# Microcontroleur.net
KiCad netlist of a schematic drawn in Altium Designer
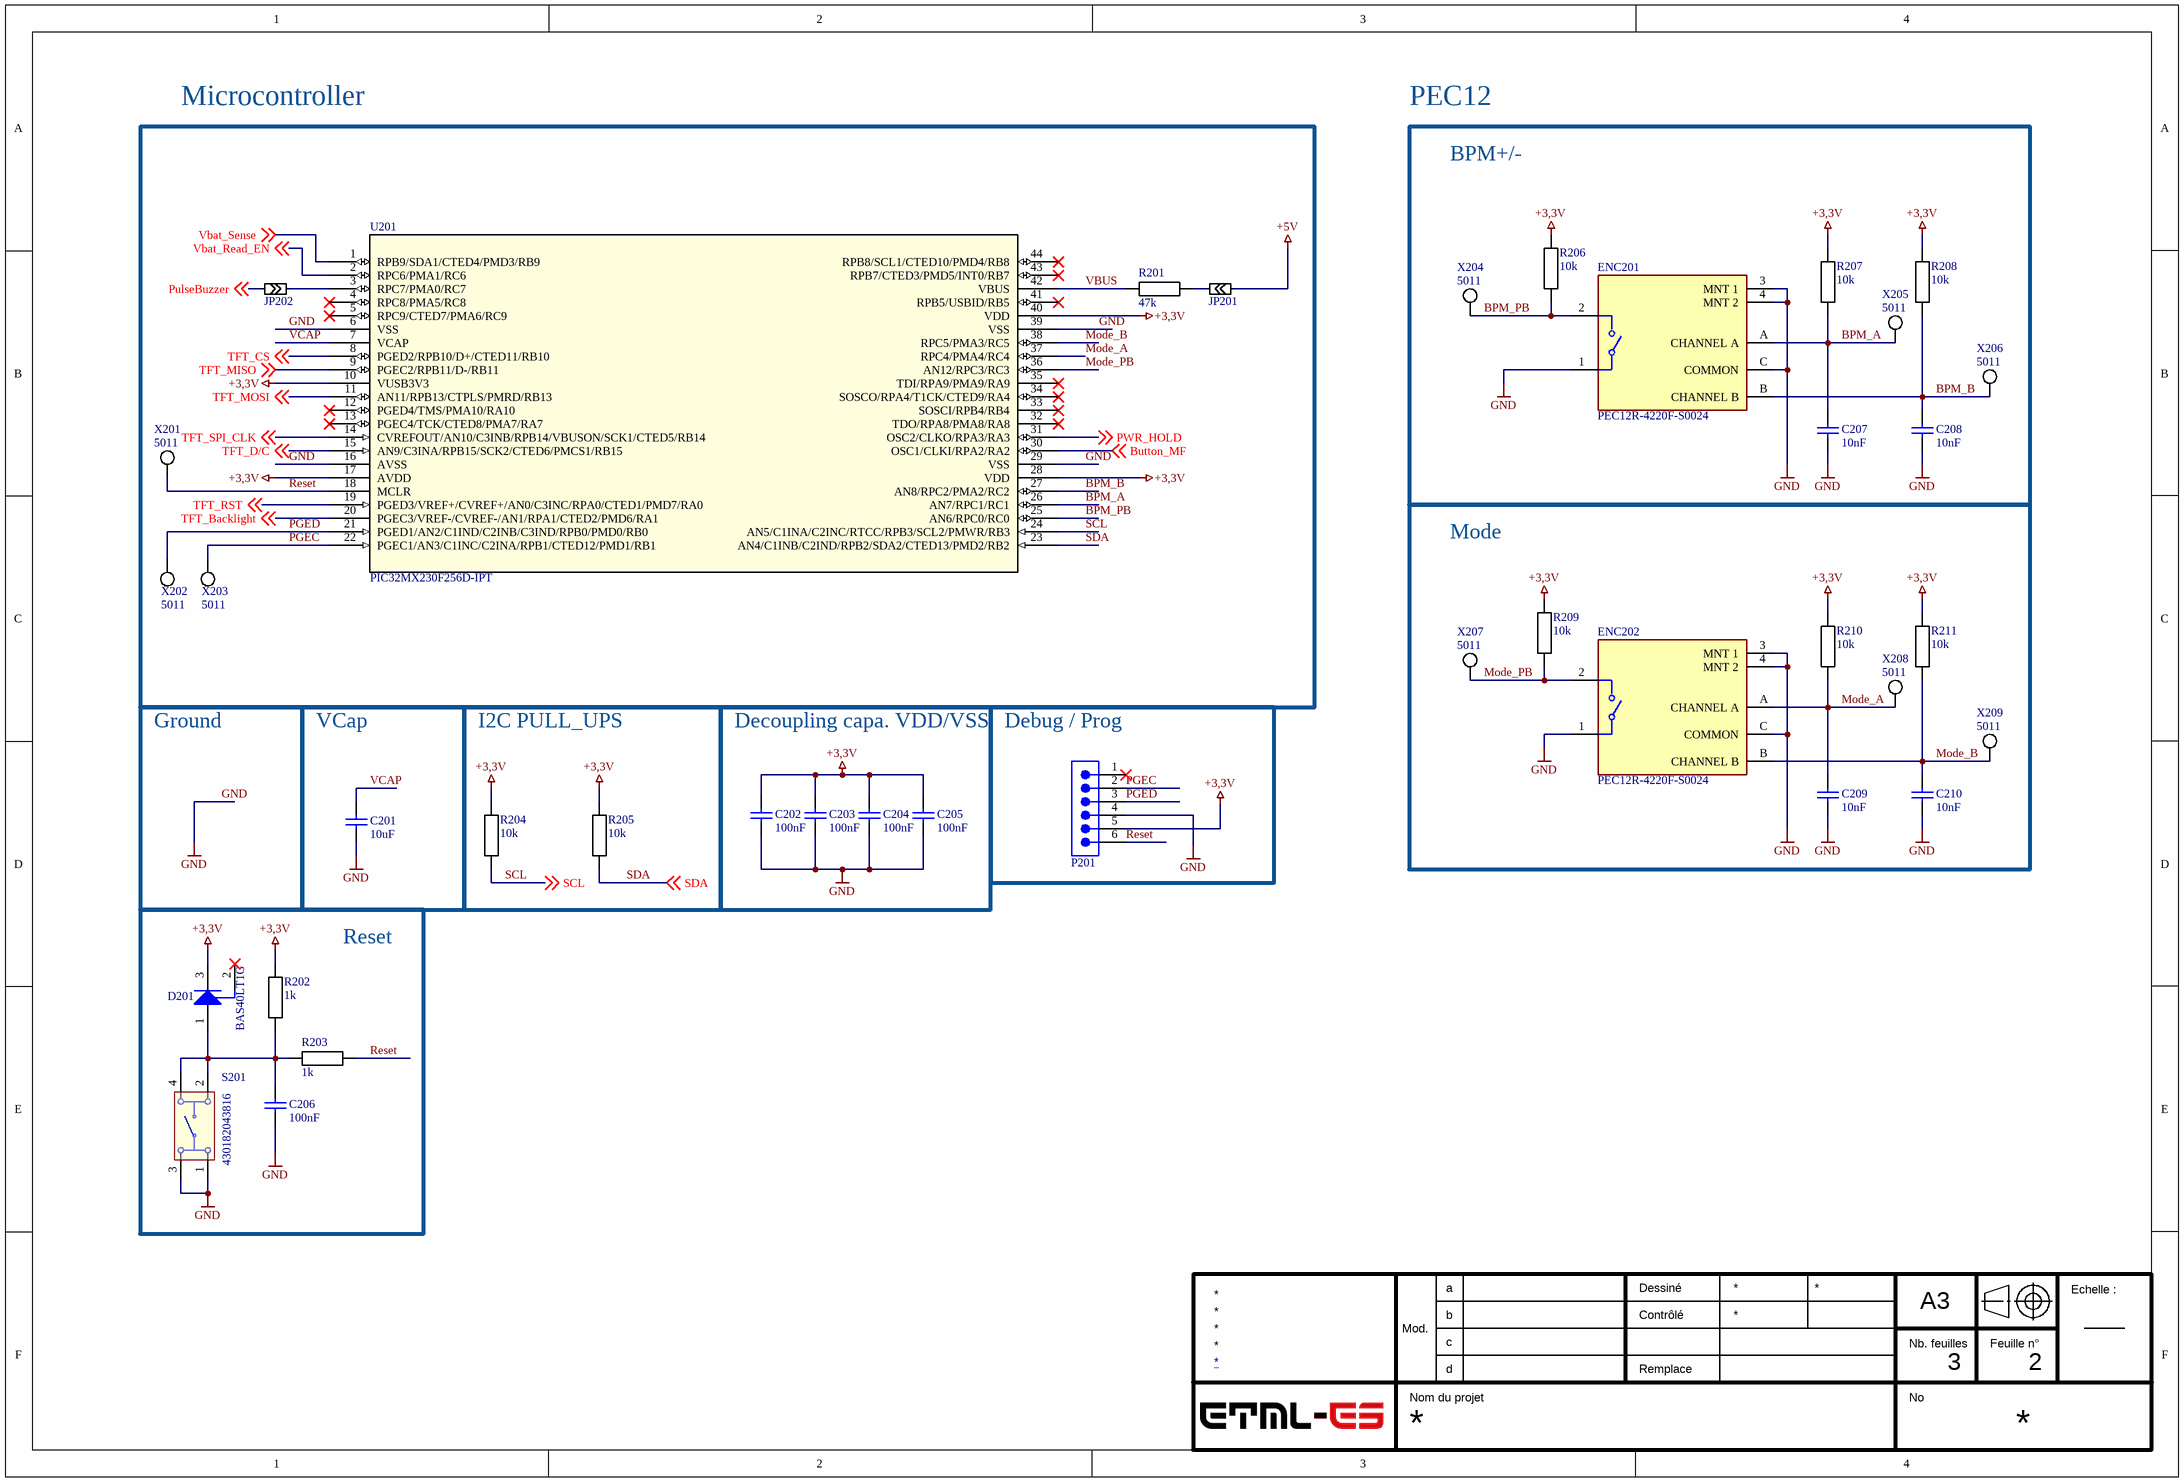
[diagram p0: Microcontroleur.SchDoc]

(export (version "E")
  (design (tool "Eeschema 10.0.6"))
  (components
    (comp (ref "C201")
      (value "10uF")
      (footprint "CAPC2012X08M")
      (description "Capacitor")
      (fields (field (name "Comment") "Cap") (field (name "PUBLISHER") "Altium Limited"))
      (libsource (lib "Miscellaneous Devices") (part "Cap"))
    )
    (comp (ref "C202")
      (value "100nF")
      (footprint "CAPC2012X08M")
      (description "Capacitor")
      (fields (field (name "Comment") "Cap") (field (name "PUBLISHER") "Altium Limited"))
      (libsource (lib "Miscellaneous Devices") (part "Cap"))
    )
    (comp (ref "C203")
      (value "100nF")
      (footprint "CAPC2012X08M")
      (description "Capacitor")
      (fields (field (name "Comment") "Cap") (field (name "PUBLISHER") "Altium Limited"))
      (libsource (lib "Miscellaneous Devices") (part "Cap"))
    )
    (comp (ref "C204")
      (value "100nF")
      (footprint "CAPC2012X08M")
      (description "Capacitor")
      (fields (field (name "Comment") "Cap") (field (name "PUBLISHER") "Altium Limited"))
      (libsource (lib "Miscellaneous Devices") (part "Cap"))
    )
    (comp (ref "C205")
      (value "100nF")
      (footprint "CAPC2012X08M")
      (description "Capacitor")
      (fields (field (name "Comment") "Cap") (field (name "PUBLISHER") "Altium Limited"))
      (libsource (lib "Miscellaneous Devices") (part "Cap"))
    )
    (comp (ref "C206")
      (value "100nF")
      (footprint "CAPC2012X08M")
      (description "Capacitor")
      (fields (field (name "Comment") "Cap") (field (name "PUBLISHER") "Altium Limited"))
      (libsource (lib "Miscellaneous Devices") (part "Cap"))
    )
    (comp (ref "C207")
      (value "10nF")
      (footprint "CAPC2012X08M")
      (description "Capacitor")
      (fields (field (name "Comment") "Cap") (field (name "PUBLISHER") "Altium Limited"))
      (libsource (lib "Miscellaneous Devices") (part "Cap"))
    )
    (comp (ref "C208")
      (value "10nF")
      (footprint "CAPC2012X08M")
      (description "Capacitor")
      (fields (field (name "Comment") "Cap") (field (name "PUBLISHER") "Altium Limited"))
      (libsource (lib "Miscellaneous Devices") (part "Cap"))
    )
    (comp (ref "C209")
      (value "10nF")
      (footprint "CAPC2012X08M")
      (description "Capacitor")
      (fields (field (name "Comment") "Cap") (field (name "PUBLISHER") "Altium Limited"))
      (libsource (lib "Miscellaneous Devices") (part "Cap"))
    )
    (comp (ref "C210")
      (value "10nF")
      (footprint "CAPC2012X08M")
      (description "Capacitor")
      (fields (field (name "Comment") "Cap") (field (name "PUBLISHER") "Altium Limited"))
      (libsource (lib "Miscellaneous Devices") (part "Cap"))
    )
    (comp (ref "D201")
      (value "BAS40LT1G")
      (footprint "ONSC-SOT-23-3-318-08_V")
      (description "Schottky Barrier Diode, 3-Pin SOT-23, Pb-Free, Tape and Reel")
      (fields (field (name "MANUFACTURER") "On Semiconductor"))
      (libsource (lib "Altium Content Vault") (part "ONSC-D-A1K3-3"))
    )
    (comp (ref "ENC201")
      (value "PEC12R-4220F-S0024")
      (footprint "FP-PEC12R-4220F-S0024-MFG")
      (description "ROTARY ENCODER MECHANICAL 24PPR")
      (libsource (lib "Altium Content Vault") (part "94c173c7df275f4241826ab5d869309"))
    )
    (comp (ref "ENC202")
      (value "PEC12R-4220F-S0024")
      (footprint "FP-PEC12R-4220F-S0024-MFG")
      (description "ROTARY ENCODER MECHANICAL 24PPR")
      (libsource (lib "Altium Content Vault") (part "94c173c7df275f4241826ab5d869309"))
    )
    (comp (ref "JP201")
      (value "Jumper Pad")
      (footprint "Jumper SMD")
      (description "SMD Jumper")
      (libsource (lib "2318_Métronome_Electronique_Library") (part "Jumper Pad"))
    )
    (comp (ref "JP202")
      (value "Jumper Pad")
      (footprint "Jumper SMD")
      (description "SMD Jumper")
      (libsource (lib "2318_Métronome_Electronique_Library") (part "Jumper Pad"))
    )
    (comp (ref "P201")
      (value "61300611121")
      (footprint "61300611121")
      (description "WR-PHD Pin Header, THT, Vertical, pitch 2.54mm, 1 Row, 6P")
      (fields (field (name "MANUFACTURER") "Wurth Elektronik"))
      (libsource (lib "2318_Métronome_Electronique_Library") (part "61300611121"))
    )
    (comp (ref "R201")
      (value "47k")
      (footprint "RESC2012X06M")
      (description "RES 47kohm  ±1% 0.125W 2012 (0805 INCH)")
      (fields (field (name "MANUFACTURER") "Yageo") (field (name "VOLTAGE") "150V"))
      (libsource (lib "ETML-ES") (part "RES"))
    )
    (comp (ref "R202")
      (value "1k")
      (footprint "RESC2012X06M")
      (description "RES 1.0kohm  ±1% 0.125W 2012 (0805 INCH)")
      (fields (field (name "MANUFACTURER") "Yageo") (field (name "TOLERANCE") "±1%"))
      (libsource (lib "ETML-ES") (part "RES"))
    )
    (comp (ref "R203")
      (value "1k")
      (footprint "RESC2012X06M")
      (description "RES 1.0kohm  ±1% 0.125W 2012 (0805 INCH)")
      (fields (field (name "MANUFACTURER") "Yageo") (field (name "TOLERANCE") "±1%"))
      (libsource (lib "ETML-ES") (part "RES"))
    )
    (comp (ref "R204")
      (value "10k")
      (footprint "RESC2012X06M")
      (description "RES 10kohm  ±1% 0.125W 2012 (0805 INCH)")
      (fields (field (name "TOLERANCE") "±1%") (field (name "VOLTAGE") "150V"))
      (libsource (lib "ETML-ES") (part "RES"))
    )
    (comp (ref "R205")
      (value "10k")
      (footprint "RESC2012X06M")
      (description "RES 10kohm  ±1% 0.125W 2012 (0805 INCH)")
      (fields (field (name "TOLERANCE") "±1%") (field (name "VOLTAGE") "150V"))
      (libsource (lib "ETML-ES") (part "RES"))
    )
    (comp (ref "R206")
      (value "10k")
      (footprint "RESC2012X06M")
      (description "Resistor 0805 M")
      (libsource (lib "2318_Métronome_Electronique_Library") (part "R"))
    )
    (comp (ref "R207")
      (value "10k")
      (footprint "RESC2012X06M")
      (description "Resistor 0805 M")
      (libsource (lib "2318_Métronome_Electronique_Library") (part "R"))
    )
    (comp (ref "R208")
      (value "10k")
      (footprint "RESC2012X06M")
      (description "Resistor 0805 M")
      (libsource (lib "2318_Métronome_Electronique_Library") (part "R"))
    )
    (comp (ref "R209")
      (value "10k")
      (footprint "RESC2012X06M")
      (description "Resistor 0805 M")
      (libsource (lib "2318_Métronome_Electronique_Library") (part "R"))
    )
    (comp (ref "R210")
      (value "10k")
      (footprint "RESC2012X06M")
      (description "Resistor 0805 M")
      (libsource (lib "2318_Métronome_Electronique_Library") (part "R"))
    )
    (comp (ref "R211")
      (value "10k")
      (footprint "RESC2012X06M")
      (description "Resistor 0805 M")
      (libsource (lib "2318_Métronome_Electronique_Library") (part "R"))
    )
    (comp (ref "S201")
      (value "430182043816")
      (footprint "430182043816")
      (description "WS-TASV SMD Tact Switch 6X6 mm")
      (fields (field (name "MANUFACTURER") "Wuerth Elektronik"))
      (libsource (lib "Altium Content Vault") (part "WE-TACT-SW-4"))
    )
    (comp (ref "U201")
      (value "PIC32MX230F256D-IPT")
      (footprint "TQFP44_PT_MCH")
      (description "No Description Available")
      (libsource (lib "2318_Métronome_Electronique_Library") (part "PIC32MX230F256D-IPT"))
    )
    (comp (ref "X201")
      (value "5011")
      (footprint "Keystone_5011")
      (description "TEST THT MULTIPURPOSE BK")
      (fields (field (name "MANUFACTURER") "Keystone"))
      (libsource (lib "ETML-ES") (part "TEST"))
    )
    (comp (ref "X202")
      (value "5011")
      (footprint "Keystone_5011")
      (description "TEST THT MULTIPURPOSE BK")
      (fields (field (name "MANUFACTURER") "Keystone"))
      (libsource (lib "ETML-ES") (part "TEST"))
    )
    (comp (ref "X203")
      (value "5011")
      (footprint "Keystone_5011")
      (description "TEST THT MULTIPURPOSE BK")
      (fields (field (name "MANUFACTURER") "Keystone"))
      (libsource (lib "ETML-ES") (part "TEST"))
    )
    (comp (ref "X204")
      (value "5011")
      (footprint "Keystone_5011")
      (description "TEST THT MULTIPURPOSE BK")
      (fields (field (name "MANUFACTURER") "Keystone"))
      (libsource (lib "ETML-ES") (part "TEST"))
    )
    (comp (ref "X205")
      (value "5011")
      (footprint "Keystone_5011")
      (description "TEST THT MULTIPURPOSE BK")
      (fields (field (name "MANUFACTURER") "Keystone"))
      (libsource (lib "ETML-ES") (part "TEST"))
    )
    (comp (ref "X206")
      (value "5011")
      (footprint "Keystone_5011")
      (description "TEST THT MULTIPURPOSE BK")
      (fields (field (name "MANUFACTURER") "Keystone"))
      (libsource (lib "ETML-ES") (part "TEST"))
    )
    (comp (ref "X207")
      (value "5011")
      (footprint "Keystone_5011")
      (description "TEST THT MULTIPURPOSE BK")
      (fields (field (name "MANUFACTURER") "Keystone"))
      (libsource (lib "ETML-ES") (part "TEST"))
    )
    (comp (ref "X208")
      (value "5011")
      (footprint "Keystone_5011")
      (description "TEST THT MULTIPURPOSE BK")
      (fields (field (name "MANUFACTURER") "Keystone"))
      (libsource (lib "ETML-ES") (part "TEST"))
    )
    (comp (ref "X209")
      (value "5011")
      (footprint "Keystone_5011")
      (description "TEST THT MULTIPURPOSE BK")
      (fields (field (name "MANUFACTURER") "Keystone"))
      (libsource (lib "ETML-ES") (part "TEST"))
    )
  )
  (nets
    (net (code "1") (name "+3,3V") (class "Default")
      (node (ref "C202") (pin "2") (pinfunction "2_2") (pintype "passive"))
      (node (ref "C203") (pin "2") (pinfunction "2_2") (pintype "passive"))
      (node (ref "C204") (pin "2") (pinfunction "2_2") (pintype "passive"))
      (node (ref "C205") (pin "2") (pinfunction "2_2") (pintype "passive"))
      (node (ref "D201") (pin "3") (pinfunction "K_3") (pintype "passive"))
      (node (ref "P201") (pin "5") (pinfunction "5_5") (pintype "passive"))
      (node (ref "R202") (pin "2") (pinfunction "2_2") (pintype "passive"))
      (node (ref "R204") (pin "2") (pinfunction "2_2") (pintype "passive"))
      (node (ref "R205") (pin "2") (pinfunction "2_2") (pintype "passive"))
      (node (ref "R206") (pin "1") (pinfunction "1_1") (pintype "passive"))
      (node (ref "R207") (pin "2") (pinfunction "2_2") (pintype "passive"))
      (node (ref "R208") (pin "2") (pinfunction "2_2") (pintype "passive"))
      (node (ref "R209") (pin "1") (pinfunction "1_1") (pintype "passive"))
      (node (ref "R210") (pin "2") (pinfunction "2_2") (pintype "passive"))
      (node (ref "R211") (pin "2") (pinfunction "2_2") (pintype "passive"))
      (node (ref "U201") (pin "10") (pinfunction "VUSB3V3_10") (pintype "power_in"))
      (node (ref "U201") (pin "17") (pinfunction "AVDD_17") (pintype "power_in"))
      (node (ref "U201") (pin "28") (pinfunction "VDD_28") (pintype "power_in"))
      (node (ref "U201") (pin "40") (pinfunction "VDD_40") (pintype "power_in"))
    )
    (net (code "2") (name "+5V") (class "Default")
      (node (ref "JP201") (pin "2") (pinfunction "2_2") (pintype "passive"))
    )
    (net (code "3") (name "/BPM_A") (class "Default")
      (node (ref "C207") (pin "2") (pinfunction "2_2") (pintype "passive"))
      (node (ref "ENC201") (pin "A") (pinfunction "CHANNEL_A_A") (pintype "passive"))
      (node (ref "R207") (pin "1") (pinfunction "1_1") (pintype "passive"))
      (node (ref "U201") (pin "26") (pinfunction "AN7/RPC1/RC1_26") (pintype "bidirectional"))
      (node (ref "X205") (pin "1") (pinfunction "TP_1") (pintype "passive"))
    )
    (net (code "4") (name "/BPM_B") (class "Default")
      (node (ref "C208") (pin "2") (pinfunction "2_2") (pintype "passive"))
      (node (ref "ENC201") (pin "B") (pinfunction "CHANNEL_B_B") (pintype "passive"))
      (node (ref "R208") (pin "1") (pinfunction "1_1") (pintype "passive"))
      (node (ref "U201") (pin "27") (pinfunction "AN8/RPC2/PMA2/RC2_27") (pintype "bidirectional"))
      (node (ref "X206") (pin "1") (pinfunction "TP_1") (pintype "passive"))
    )
    (net (code "5") (name "/BPM_PB") (class "Default")
      (node (ref "ENC201") (pin "2") (pinfunction "2_2") (pintype "passive"))
      (node (ref "R206") (pin "2") (pinfunction "2_2") (pintype "passive"))
      (node (ref "U201") (pin "25") (pinfunction "AN6/RPC0/RC0_25") (pintype "bidirectional"))
      (node (ref "X204") (pin "1") (pinfunction "TP_1") (pintype "passive"))
    )
    (net (code "6") (name "/Mode_A") (class "Default")
      (node (ref "C209") (pin "2") (pinfunction "2_2") (pintype "passive"))
      (node (ref "ENC202") (pin "A") (pinfunction "CHANNEL_A_A") (pintype "passive"))
      (node (ref "R210") (pin "1") (pinfunction "1_1") (pintype "passive"))
      (node (ref "U201") (pin "37") (pinfunction "RPC4/PMA4/RC4_37") (pintype "bidirectional"))
      (node (ref "X208") (pin "1") (pinfunction "TP_1") (pintype "passive"))
    )
    (net (code "7") (name "/Mode_B") (class "Default")
      (node (ref "C210") (pin "2") (pinfunction "2_2") (pintype "passive"))
      (node (ref "ENC202") (pin "B") (pinfunction "CHANNEL_B_B") (pintype "passive"))
      (node (ref "R211") (pin "1") (pinfunction "1_1") (pintype "passive"))
      (node (ref "U201") (pin "38") (pinfunction "RPC5/PMA3/RC5_38") (pintype "bidirectional"))
      (node (ref "X209") (pin "1") (pinfunction "TP_1") (pintype "passive"))
    )
    (net (code "8") (name "/Mode_PB") (class "Default")
      (node (ref "ENC202") (pin "2") (pinfunction "2_2") (pintype "passive"))
      (node (ref "R209") (pin "2") (pinfunction "2_2") (pintype "passive"))
      (node (ref "U201") (pin "36") (pinfunction "AN12/RPC3/RC3_36") (pintype "bidirectional"))
      (node (ref "X207") (pin "1") (pinfunction "TP_1") (pintype "passive"))
    )
    (net (code "9") (name "/PGEC") (class "Default")
      (node (ref "P201") (pin "2") (pinfunction "2_2") (pintype "passive"))
      (node (ref "U201") (pin "22") (pinfunction "PGEC1/AN3/C1INC/C2INA/RPB1/CTED12/PMD1/RB1_22") (pintype "input"))
      (node (ref "X203") (pin "1") (pinfunction "TP_1") (pintype "passive"))
    )
    (net (code "10") (name "/PGED") (class "Default")
      (node (ref "P201") (pin "3") (pinfunction "3_3") (pintype "passive"))
      (node (ref "U201") (pin "21") (pinfunction "PGED1/AN2/C1IND/C2INB/C3IND/RPB0/PMD0/RB0_21") (pintype "input"))
      (node (ref "X202") (pin "1") (pinfunction "TP_1") (pintype "passive"))
    )
    (net (code "11") (name "/Reset") (class "Default")
      (node (ref "P201") (pin "6") (pinfunction "6_6") (pintype "passive"))
      (node (ref "R203") (pin "1") (pinfunction "1_1") (pintype "passive"))
      (node (ref "U201") (pin "18") (pinfunction "MCLR_18") (pintype "passive"))
      (node (ref "X201") (pin "1") (pinfunction "TP_1") (pintype "passive"))
    )
    (net (code "12") (name "/VBUS") (class "Default")
      (node (ref "R201") (pin "1") (pinfunction "1_1") (pintype "passive"))
      (node (ref "U201") (pin "42") (pinfunction "VBUS_42") (pintype "passive"))
    )
    (net (code "13") (name "/VCAP") (class "Default")
      (node (ref "C201") (pin "2") (pinfunction "2_2") (pintype "passive"))
      (node (ref "U201") (pin "7") (pinfunction "VCAP_7") (pintype "power_in"))
    )
    (net (code "15") (name "Button_MF") (class "Default")
      (node (ref "U201") (pin "30") (pinfunction "OSC1/CLKI/RPA2/RA2_30") (pintype "bidirectional"))
    )
    (net (code "16") (name "GND") (class "Default")
      (node (ref "C201") (pin "1") (pinfunction "1_1") (pintype "passive"))
      (node (ref "C202") (pin "1") (pinfunction "1_1") (pintype "passive"))
      (node (ref "C203") (pin "1") (pinfunction "1_1") (pintype "passive"))
      (node (ref "C204") (pin "1") (pinfunction "1_1") (pintype "passive"))
      (node (ref "C205") (pin "1") (pinfunction "1_1") (pintype "passive"))
      (node (ref "C206") (pin "1") (pinfunction "1_1") (pintype "passive"))
      (node (ref "C207") (pin "1") (pinfunction "1_1") (pintype "passive"))
      (node (ref "C208") (pin "1") (pinfunction "1_1") (pintype "passive"))
      (node (ref "C209") (pin "1") (pinfunction "1_1") (pintype "passive"))
      (node (ref "C210") (pin "1") (pinfunction "1_1") (pintype "passive"))
      (node (ref "ENC201") (pin "1") (pinfunction "1_1") (pintype "passive"))
      (node (ref "ENC201") (pin "3") (pinfunction "MNT_1_3") (pintype "passive"))
      (node (ref "ENC201") (pin "4") (pinfunction "MNT_2_4") (pintype "passive"))
      (node (ref "ENC201") (pin "C") (pinfunction "COMMON_C") (pintype "passive"))
      (node (ref "ENC202") (pin "1") (pinfunction "1_1") (pintype "passive"))
      (node (ref "ENC202") (pin "3") (pinfunction "MNT_1_3") (pintype "passive"))
      (node (ref "ENC202") (pin "4") (pinfunction "MNT_2_4") (pintype "passive"))
      (node (ref "ENC202") (pin "C") (pinfunction "COMMON_C") (pintype "passive"))
      (node (ref "P201") (pin "4") (pinfunction "4_4") (pintype "passive"))
      (node (ref "S201") (pin "1") (pinfunction "1_1") (pintype "passive"))
      (node (ref "S201") (pin "3") (pinfunction "3_3") (pintype "passive"))
      (node (ref "U201") (pin "16") (pinfunction "AVSS_16") (pintype "power_in"))
      (node (ref "U201") (pin "29") (pinfunction "VSS_29") (pintype "power_in"))
      (node (ref "U201") (pin "39") (pinfunction "VSS_39") (pintype "power_in"))
      (node (ref "U201") (pin "6") (pinfunction "VSS_6") (pintype "power_in"))
    )
    (net (code "17") (name "Net-(D201-A)") (class "Default")
      (node (ref "C206") (pin "2") (pinfunction "2_2") (pintype "passive"))
      (node (ref "D201") (pin "1") (pinfunction "A_1") (pintype "passive"))
      (node (ref "R202") (pin "1") (pinfunction "1_1") (pintype "passive"))
      (node (ref "R203") (pin "2") (pinfunction "2_2") (pintype "passive"))
      (node (ref "S201") (pin "2") (pinfunction "2_2") (pintype "passive"))
      (node (ref "S201") (pin "4") (pinfunction "4_4") (pintype "passive"))
    )
    (net (code "18") (name "Net-(JP201-Pad1)") (class "Default")
      (node (ref "JP201") (pin "1") (pinfunction "1_1") (pintype "passive"))
      (node (ref "R201") (pin "2") (pinfunction "2_2") (pintype "passive"))
    )
    (net (code "19") (name "Net-(U201-RPC7{slash}PMA0{slash}RC7)") (class "Default")
      (node (ref "JP202") (pin "1") (pinfunction "1_1") (pintype "passive"))
      (node (ref "U201") (pin "3") (pinfunction "RPC7/PMA0/RC7_3") (pintype "bidirectional"))
    )
    (net (code "20") (name "PWR_HOLD") (class "Default")
      (node (ref "U201") (pin "31") (pinfunction "OSC2/CLKO/RPA3/RA3_31") (pintype "bidirectional"))
    )
    (net (code "21") (name "PulseBuzzer") (class "Default")
      (node (ref "JP202") (pin "2") (pinfunction "2_2") (pintype "passive"))
    )
    (net (code "22") (name "SCL") (class "Default")
      (node (ref "R204") (pin "1") (pinfunction "1_1") (pintype "passive"))
      (node (ref "U201") (pin "24") (pinfunction "AN5/C1INA/C2INC/RTCC/RPB3/SCL2/PMWR/RB3_24") (pintype "input"))
    )
    (net (code "23") (name "SDA") (class "Default")
      (node (ref "R205") (pin "1") (pinfunction "1_1") (pintype "passive"))
      (node (ref "U201") (pin "23") (pinfunction "AN4/C1INB/C2IND/RPB2/SDA2/CTED13/PMD2/RB2_23") (pintype "input"))
    )
    (net (code "24") (name "TFT_Backlight") (class "Default")
      (node (ref "U201") (pin "20") (pinfunction "PGEC3/VREF-/CVREF-/AN1/RPA1/CTED2/PMD6/RA1_20") (pintype "power_in"))
    )
    (net (code "25") (name "TFT_CS") (class "Default")
      (node (ref "U201") (pin "8") (pinfunction "PGED2/RPB10/D+/CTED11/RB10_8") (pintype "bidirectional"))
    )
    (net (code "26") (name "TFT_D{slash}C") (class "Default")
      (node (ref "U201") (pin "15") (pinfunction "AN9/C3INA/RPB15/SCK2/CTED6/PMCS1/RB15_15") (pintype "input"))
    )
    (net (code "27") (name "TFT_MISO") (class "Default")
      (node (ref "U201") (pin "9") (pinfunction "PGEC2/RPB11/D-/RB11_9") (pintype "bidirectional"))
    )
    (net (code "28") (name "TFT_MOSI") (class "Default")
      (node (ref "U201") (pin "11") (pinfunction "AN11/RPB13/CTPLS/PMRD/RB13_11") (pintype "bidirectional"))
    )
    (net (code "29") (name "TFT_RST") (class "Default")
      (node (ref "U201") (pin "19") (pinfunction "PGED3/VREF+/CVREF+/AN0/C3INC/RPA0/CTED1/PMD7/RA0_19") (pintype "input"))
    )
    (net (code "30") (name "TFT_SPI_CLK") (class "Default")
      (node (ref "U201") (pin "14") (pinfunction "CVREFOUT/AN10/C3INB/RPB14/VBUSON/SCK1/CTED5/RB14_14") (pintype "input"))
    )
    (net (code "31") (name "Vbat_Read_EN") (class "Default")
      (node (ref "U201") (pin "2") (pinfunction "RPC6/PMA1/RC6_2") (pintype "bidirectional"))
    )
    (net (code "32") (name "Vbat_Sense") (class "Default")
      (node (ref "U201") (pin "1") (pinfunction "RPB9/SDA1/CTED4/PMD3/RB9_1") (pintype "bidirectional"))
    )
    (net (code "33") (name "unconnected-(D201-NC-Pad2)") (class "Default")
      (node (ref "D201") (pin "2") (pinfunction "NC_2") (pintype "passive+no_connect"))
    )
    (net (code "34") (name "unconnected-(P201-Pad1)") (class "Default")
      (node (ref "P201") (pin "1") (pinfunction "1_1") (pintype "passive+no_connect"))
    )
    (net (code "35") (name "unconnected-(U201-PGEC4{slash}TCK{slash}CTED8{slash}PMA7{slash}RA7-Pad13)") (class "Default")
      (node (ref "U201") (pin "13") (pinfunction "PGEC4/TCK/CTED8/PMA7/RA7_13") (pintype "bidirectional+no_connect"))
    )
    (net (code "36") (name "unconnected-(U201-PGED4{slash}TMS{slash}PMA10{slash}RA10-Pad12)") (class "Default")
      (node (ref "U201") (pin "12") (pinfunction "PGED4/TMS/PMA10/RA10_12") (pintype "bidirectional+no_connect"))
    )
    (net (code "37") (name "unconnected-(U201-RPB5{slash}USBID{slash}RB5-Pad41)") (class "Default")
      (node (ref "U201") (pin "41") (pinfunction "RPB5/USBID/RB5_41") (pintype "bidirectional+no_connect"))
    )
    (net (code "38") (name "unconnected-(U201-RPB7{slash}CTED3{slash}PMD5{slash}INT0{slash}RB7-Pad43)") (class "Default")
      (node (ref "U201") (pin "43") (pinfunction "RPB7/CTED3/PMD5/INT0/RB7_43") (pintype "bidirectional+no_connect"))
    )
    (net (code "39") (name "unconnected-(U201-RPB8{slash}SCL1{slash}CTED10{slash}PMD4{slash}RB8-Pad44)") (class "Default")
      (node (ref "U201") (pin "44") (pinfunction "RPB8/SCL1/CTED10/PMD4/RB8_44") (pintype "bidirectional+no_connect"))
    )
    (net (code "40") (name "unconnected-(U201-RPC8{slash}PMA5{slash}RC8-Pad4)") (class "Default")
      (node (ref "U201") (pin "4") (pinfunction "RPC8/PMA5/RC8_4") (pintype "bidirectional+no_connect"))
    )
    (net (code "41") (name "unconnected-(U201-RPC9{slash}CTED7{slash}PMA6{slash}RC9-Pad5)") (class "Default")
      (node (ref "U201") (pin "5") (pinfunction "RPC9/CTED7/PMA6/RC9_5") (pintype "bidirectional+no_connect"))
    )
    (net (code "42") (name "unconnected-(U201-SOSCI{slash}RPB4{slash}RB4-Pad33)") (class "Default")
      (node (ref "U201") (pin "33") (pinfunction "SOSCI/RPB4/RB4_33") (pintype "passive+no_connect"))
    )
    (net (code "43") (name "unconnected-(U201-SOSCO{slash}RPA4{slash}T1CK{slash}CTED9{slash}RA4-Pad34)") (class "Default")
      (node (ref "U201") (pin "34") (pinfunction "SOSCO/RPA4/T1CK/CTED9/RA4_34") (pintype "bidirectional+no_connect"))
    )
    (net (code "44") (name "unconnected-(U201-TDI{slash}RPA9{slash}PMA9{slash}RA9-Pad35)") (class "Default")
      (node (ref "U201") (pin "35") (pinfunction "TDI/RPA9/PMA9/RA9_35") (pintype "passive+no_connect"))
    )
    (net (code "45") (name "unconnected-(U201-TDO{slash}RPA8{slash}PMA8{slash}RA8-Pad32)") (class "Default")
      (node (ref "U201") (pin "32") (pinfunction "TDO/RPA8/PMA8/RA8_32") (pintype "passive+no_connect"))
    )
  )
)
